# Mcontr_3.net
KiCad netlist of a schematic drawn in Altium Designer
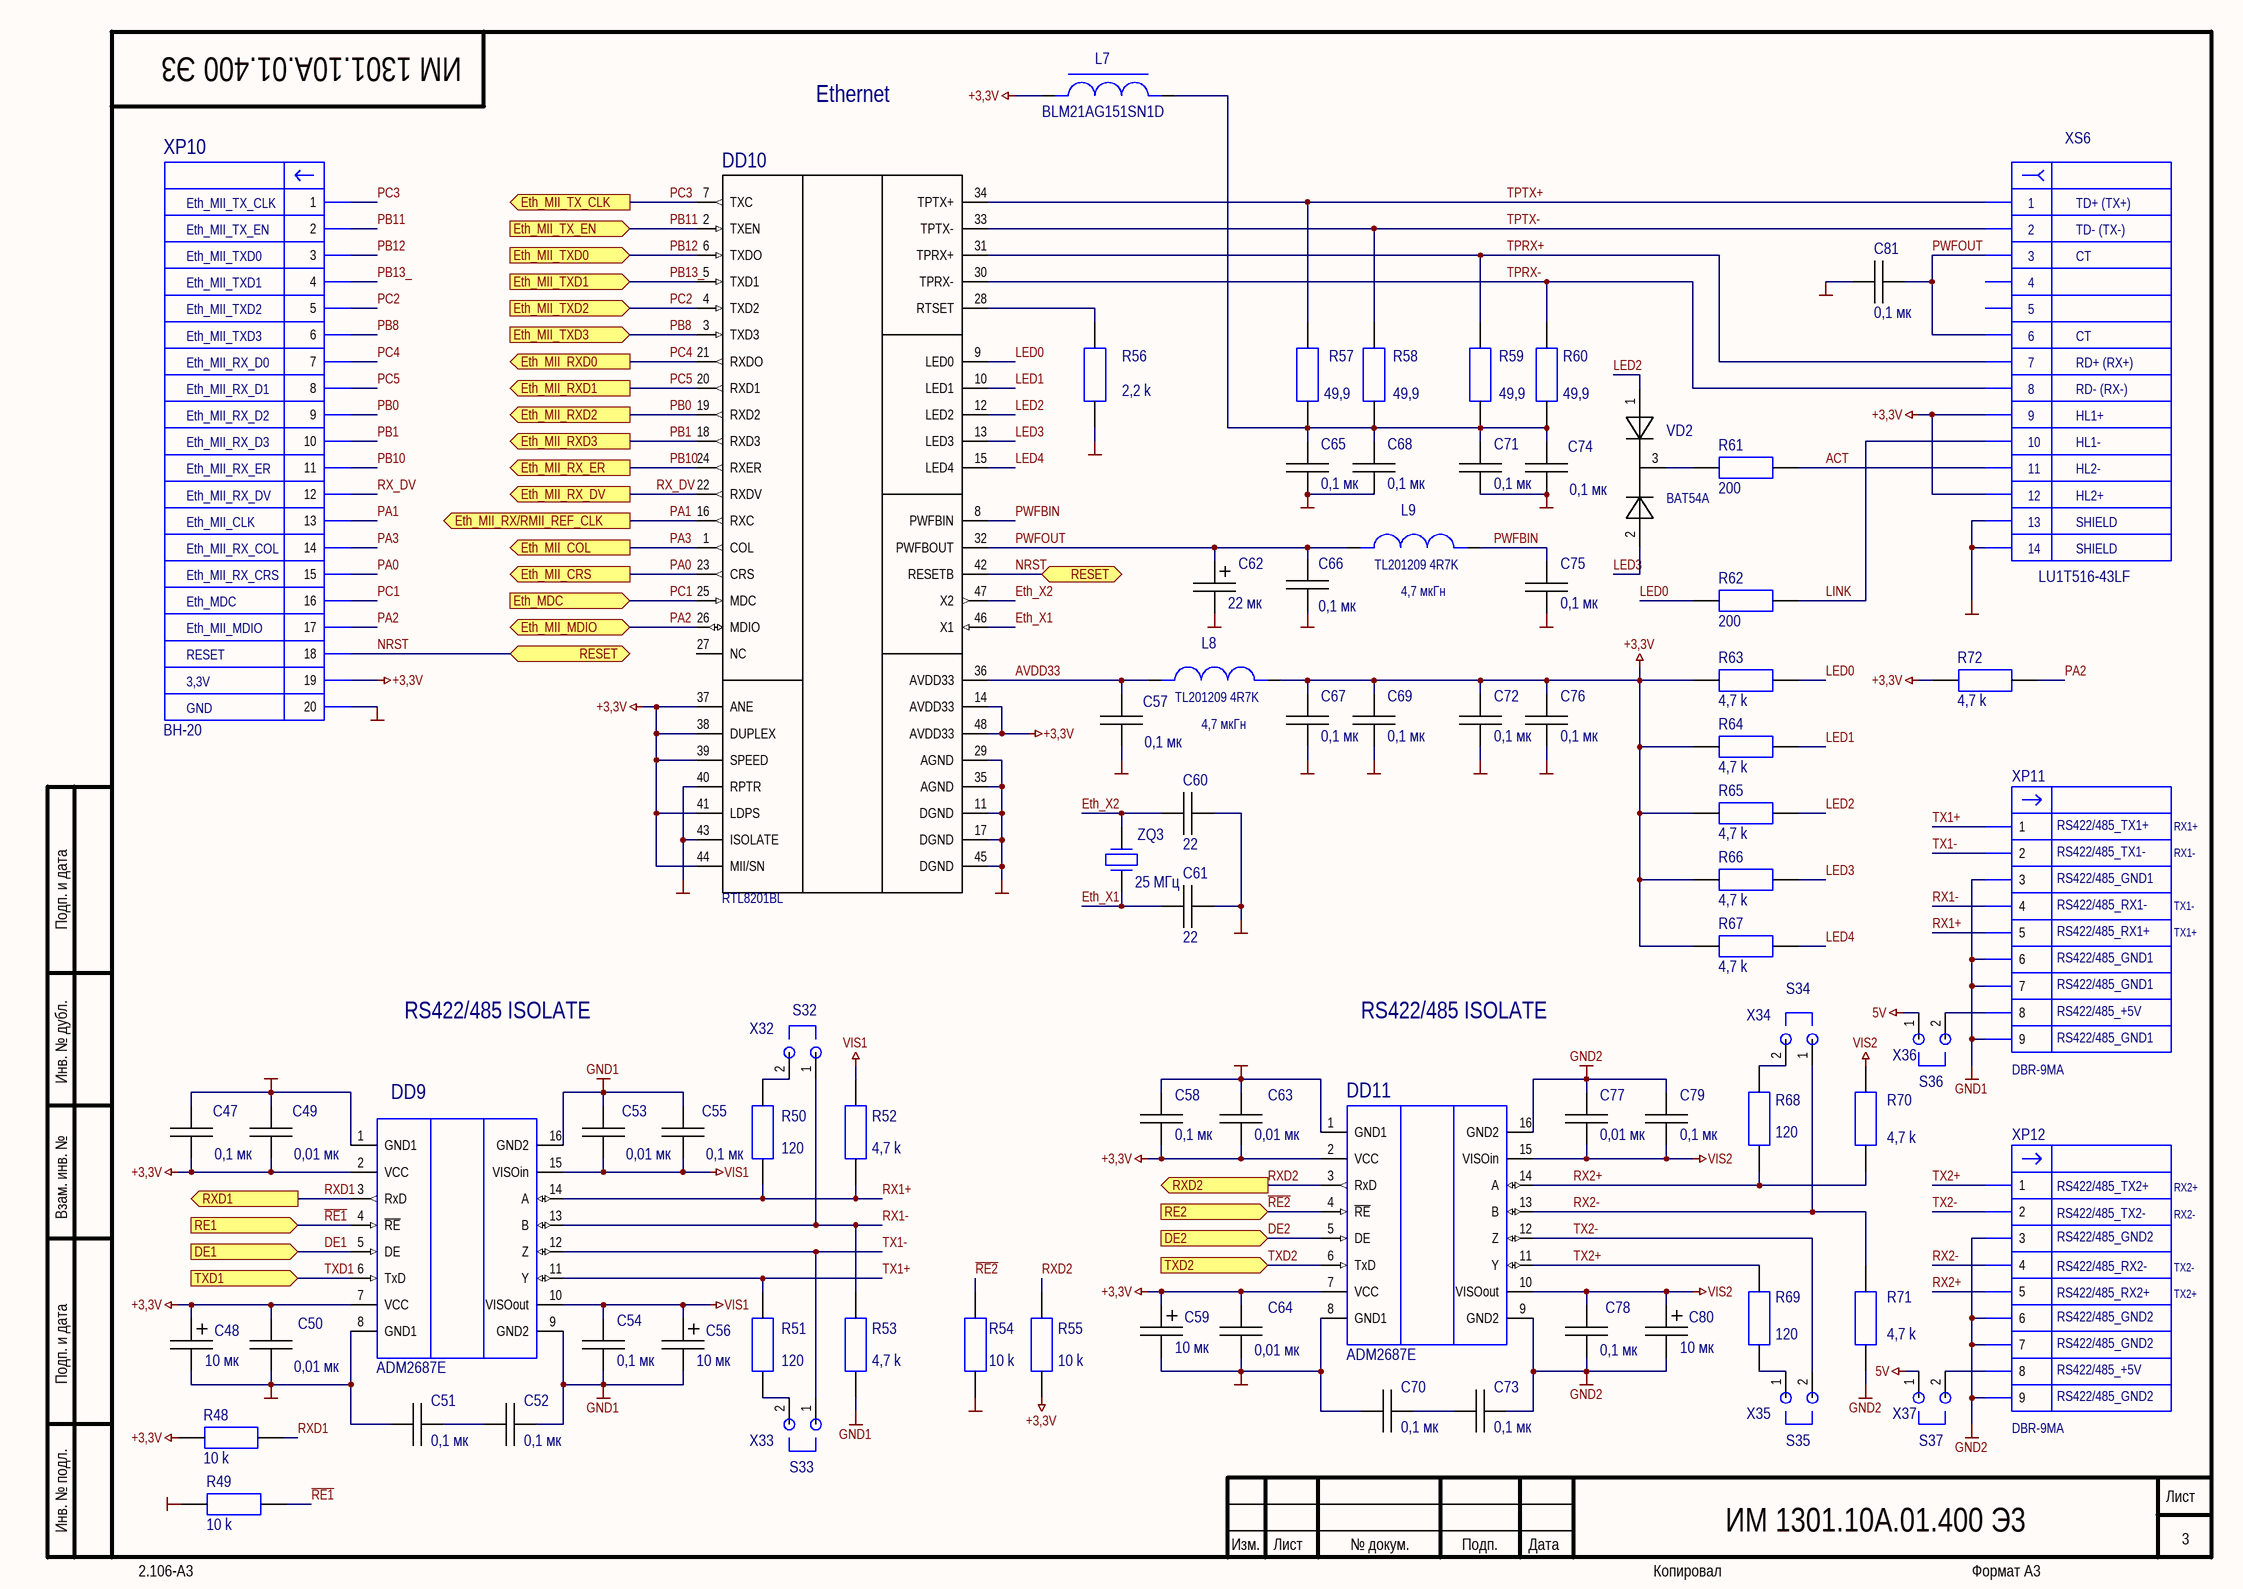
[diagram p0: Mcontr_3.SchDoc]

(export (version "E")
  (design (tool "Eeschema 10.0.6"))
  (components
    (comp (ref "C47")
      (value "0,1 мк")
      (footprint "CAPC_1206")
      (description "Capasitor")
      (fields (field (name "PART NUMBER") "C"))
      (libsource (lib "RLC_GOST") (part "C"))
    )
    (comp (ref "C48")
      (value "10 мк")
      (footprint "3216")
      (description "Capasitor_polar")
      (fields (field (name "PART NUMBER") "CapPol"))
      (libsource (lib "RLC_GOST") (part "CapPol"))
    )
    (comp (ref "C49")
      (value "0,01 мк")
      (footprint "CAPC_1206")
      (description "Capasitor")
      (fields (field (name "PART NUMBER") "C"))
      (libsource (lib "RLC_GOST") (part "C"))
    )
    (comp (ref "C50")
      (value "0,01 мк")
      (footprint "CAPC_1206")
      (description "Capasitor")
      (fields (field (name "PART NUMBER") "C"))
      (libsource (lib "RLC_GOST") (part "C"))
    )
    (comp (ref "C51")
      (value "0,1 мк")
      (footprint "CAPC_1206")
      (description "Capasitor")
      (fields (field (name "PART NUMBER") "C"))
      (libsource (lib "RLC_GOST") (part "C"))
    )
    (comp (ref "C52")
      (value "0,1 мк")
      (footprint "CAPC_1206")
      (description "Capasitor")
      (fields (field (name "PART NUMBER") "C"))
      (libsource (lib "RLC_GOST") (part "C"))
    )
    (comp (ref "C53")
      (value "0,01 мк")
      (footprint "CAPC_1206")
      (description "Capasitor")
      (fields (field (name "PART NUMBER") "C"))
      (libsource (lib "RLC_GOST") (part "C"))
    )
    (comp (ref "C54")
      (value "0,1 мк")
      (footprint "CAPC_1206")
      (description "Capasitor")
      (fields (field (name "PART NUMBER") "C"))
      (libsource (lib "RLC_GOST") (part "C"))
    )
    (comp (ref "C55")
      (value "0,1 мк")
      (footprint "CAPC_1206")
      (description "Capasitor")
      (fields (field (name "PART NUMBER") "C"))
      (libsource (lib "RLC_GOST") (part "C"))
    )
    (comp (ref "C56")
      (value "10 мк")
      (footprint "3216")
      (description "Capasitor_polar")
      (fields (field (name "PART NUMBER") "CapPol"))
      (libsource (lib "RLC_GOST") (part "CapPol"))
    )
    (comp (ref "C57")
      (value "0,1 мк")
      (footprint "CAPC_1206")
      (description "Capasitor")
      (fields (field (name "PART NUMBER") "C"))
      (libsource (lib "RLC_GOST") (part "C"))
    )
    (comp (ref "C58")
      (value "0,1 мк")
      (footprint "CAPC_1206")
      (description "Capasitor")
      (fields (field (name "PART NUMBER") "C"))
      (libsource (lib "RLC_GOST") (part "C"))
    )
    (comp (ref "C59")
      (value "10 мк")
      (footprint "3216")
      (description "Capasitor_polar")
      (fields (field (name "PART NUMBER") "CapPol"))
      (libsource (lib "RLC_GOST") (part "CapPol"))
    )
    (comp (ref "C60")
      (value "22")
      (footprint "CAPC_1206")
      (description "Capasitor")
      (libsource (lib "RLC_GOST") (part "C"))
    )
    (comp (ref "C61")
      (value "22")
      (footprint "CAPC_1206")
      (description "Capasitor")
      (libsource (lib "RLC_GOST") (part "C"))
    )
    (comp (ref "C62")
      (value "22 мк")
      (footprint "3216")
      (description "Capasitor_polar")
      (fields (field (name "PART NUMBER") "CapPol"))
      (libsource (lib "RLC_GOST") (part "CapPol"))
    )
    (comp (ref "C63")
      (value "0,01 мк")
      (footprint "CAPC_1206")
      (description "Capasitor")
      (fields (field (name "PART NUMBER") "C"))
      (libsource (lib "RLC_GOST") (part "C"))
    )
    (comp (ref "C64")
      (value "0,01 мк")
      (footprint "CAPC_1206")
      (description "Capasitor")
      (fields (field (name "PART NUMBER") "C"))
      (libsource (lib "RLC_GOST") (part "C"))
    )
    (comp (ref "C65")
      (value "0,1 мк")
      (footprint "CAPC_1206")
      (description "Capasitor")
      (fields (field (name "PART NUMBER") "C"))
      (libsource (lib "RLC_GOST") (part "C"))
    )
    (comp (ref "C66")
      (value "0,1 мк")
      (footprint "CAPC_1206")
      (description "Capasitor")
      (fields (field (name "PART NUMBER") "C"))
      (libsource (lib "RLC_GOST") (part "C"))
    )
    (comp (ref "C67")
      (value "0,1 мк")
      (footprint "CAPC_1206")
      (description "Capasitor")
      (fields (field (name "PART NUMBER") "C"))
      (libsource (lib "RLC_GOST") (part "C"))
    )
    (comp (ref "C68")
      (value "0,1 мк")
      (footprint "CAPC_1206")
      (description "Capasitor")
      (fields (field (name "PART NUMBER") "C"))
      (libsource (lib "RLC_GOST") (part "C"))
    )
    (comp (ref "C69")
      (value "0,1 мк")
      (footprint "CAPC_1206")
      (description "Capasitor")
      (fields (field (name "PART NUMBER") "C"))
      (libsource (lib "RLC_GOST") (part "C"))
    )
    (comp (ref "C70")
      (value "0,1 мк")
      (footprint "CAPC_1206")
      (description "Capasitor")
      (fields (field (name "PART NUMBER") "C"))
      (libsource (lib "RLC_GOST") (part "C"))
    )
    (comp (ref "C71")
      (value "0,1 мк")
      (footprint "CAPC_1206")
      (description "Capasitor")
      (fields (field (name "PART NUMBER") "C"))
      (libsource (lib "RLC_GOST") (part "C"))
    )
    (comp (ref "C72")
      (value "0,1 мк")
      (footprint "CAPC_1206")
      (description "Capasitor")
      (fields (field (name "PART NUMBER") "C"))
      (libsource (lib "RLC_GOST") (part "C"))
    )
    (comp (ref "C73")
      (value "0,1 мк")
      (footprint "CAPC_1206")
      (description "Capasitor")
      (fields (field (name "PART NUMBER") "C"))
      (libsource (lib "RLC_GOST") (part "C"))
    )
    (comp (ref "C74")
      (value "0,1 мк")
      (footprint "CAPC_1206")
      (description "Capasitor")
      (fields (field (name "PART NUMBER") "C"))
      (libsource (lib "RLC_GOST") (part "C"))
    )
    (comp (ref "C75")
      (value "0,1 мк")
      (footprint "CAPC_1206")
      (description "Capasitor")
      (fields (field (name "PART NUMBER") "C"))
      (libsource (lib "RLC_GOST") (part "C"))
    )
    (comp (ref "C76")
      (value "0,1 мк")
      (footprint "CAPC_1206")
      (description "Capasitor")
      (fields (field (name "PART NUMBER") "C"))
      (libsource (lib "RLC_GOST") (part "C"))
    )
    (comp (ref "C77")
      (value "0,01 мк")
      (footprint "CAPC_1206")
      (description "Capasitor")
      (fields (field (name "PART NUMBER") "C"))
      (libsource (lib "RLC_GOST") (part "C"))
    )
    (comp (ref "C78")
      (value "0,1 мк")
      (footprint "CAPC_1206")
      (description "Capasitor")
      (fields (field (name "PART NUMBER") "C"))
      (libsource (lib "RLC_GOST") (part "C"))
    )
    (comp (ref "C79")
      (value "0,1 мк")
      (footprint "CAPC_1206")
      (description "Capasitor")
      (fields (field (name "PART NUMBER") "C"))
      (libsource (lib "RLC_GOST") (part "C"))
    )
    (comp (ref "C80")
      (value "10 мк")
      (footprint "3216")
      (description "Capasitor_polar")
      (fields (field (name "PART NUMBER") "CapPol"))
      (libsource (lib "RLC_GOST") (part "CapPol"))
    )
    (comp (ref "C81")
      (value "0,1 мк")
      (footprint "CAPC_1206")
      (description "Capasitor")
      (fields (field (name "PART NUMBER") "C"))
      (libsource (lib "RLC_GOST") (part "C"))
    )
    (comp (ref "DD9")
      (value "ADM2687E")
      (footprint "SOIC_IC16")
      (description "RS422/RS485 transceivier 15 kV ESD Protection")
      (libsource (lib "Communication transceiver") (part "ADM2682E"))
    )
    (comp (ref "DD10")
      (value "RTL8201BL")
      (footprint "SQFP48")
      (description "Ethernet phyciever, 10/100M")
      (libsource (lib "Ethernet") (part "RTL8201BL"))
    )
    (comp (ref "DD11")
      (value "ADM2687E")
      (footprint "SOIC_IC16")
      (description "RS422/RS485 transceivier 15 kV ESD Protection")
      (libsource (lib "Communication transceiver") (part "ADM2682E"))
    )
    (comp (ref "L7")
      (value "BLM21AG151SN1D")
      (footprint "C0805")
      (description "Ferrite bead")
      (libsource (lib "RLC_GOST") (part "B"))
    )
    (comp (ref "L8")
      (value "TL201209 4R7K")
      (footprint "C0805")
      (description "Inductance")
      (fields (field (name "VALUE1") "4,7 мкГн"))
      (libsource (lib "RLC_GOST") (part "L"))
    )
    (comp (ref "L9")
      (value "TL201209 4R7K")
      (footprint "C0805")
      (description "Inductance")
      (fields (field (name "VALUE1") "4,7 мкГн"))
      (libsource (lib "RLC_GOST") (part "L"))
    )
    (comp (ref "R48")
      (value "10 k")
      (footprint "SMD_1206")
      (description "Resistor,2 Pin")
      (libsource (lib "RLC_GOST") (part "R_Gost"))
    )
    (comp (ref "R49")
      (value "10 k")
      (footprint "SMD_1206")
      (description "Resistor,2 Pin")
      (libsource (lib "RLC_GOST") (part "R_Gost"))
    )
    (comp (ref "R50")
      (value "120")
      (footprint "SMD_1206")
      (description "Resistor,2 Pin")
      (libsource (lib "RLC_GOST") (part "R_Gost"))
    )
    (comp (ref "R51")
      (value "120")
      (footprint "SMD_1206")
      (description "Resistor,2 Pin")
      (libsource (lib "RLC_GOST") (part "R_Gost"))
    )
    (comp (ref "R52")
      (value "4,7 k")
      (footprint "SMD_1206")
      (description "Resistor,2 Pin")
      (libsource (lib "RLC_GOST") (part "R_Gost"))
    )
    (comp (ref "R53")
      (value "4,7 k")
      (footprint "SMD_1206")
      (description "Resistor,2 Pin")
      (libsource (lib "RLC_GOST") (part "R_Gost"))
    )
    (comp (ref "R54")
      (value "10 k")
      (footprint "SMD_1206")
      (description "Resistor,2 Pin")
      (libsource (lib "RLC_GOST") (part "R_Gost"))
    )
    (comp (ref "R55")
      (value "10 k")
      (footprint "SMD_1206")
      (description "Resistor,2 Pin")
      (libsource (lib "RLC_GOST") (part "R_Gost"))
    )
    (comp (ref "R56")
      (value "2,2 k")
      (footprint "SMD_1206")
      (description "Resistor,2 Pin")
      (libsource (lib "RLC_GOST") (part "R_Gost"))
    )
    (comp (ref "R57")
      (value "49,9")
      (footprint "SMD_1206")
      (description "Resistor,2 Pin")
      (libsource (lib "RLC_GOST") (part "R_Gost"))
    )
    (comp (ref "R58")
      (value "49,9")
      (footprint "SMD_1206")
      (description "Resistor,2 Pin")
      (libsource (lib "RLC_GOST") (part "R_Gost"))
    )
    (comp (ref "R59")
      (value "49,9")
      (footprint "SMD_1206")
      (description "Resistor,2 Pin")
      (libsource (lib "RLC_GOST") (part "R_Gost"))
    )
    (comp (ref "R60")
      (value "49,9")
      (footprint "SMD_1206")
      (description "Resistor,2 Pin")
      (libsource (lib "RLC_GOST") (part "R_Gost"))
    )
    (comp (ref "R61")
      (value "200")
      (footprint "SMD_1206")
      (description "Resistor,2 Pin")
      (libsource (lib "RLC_GOST") (part "R_Gost"))
    )
    (comp (ref "R62")
      (value "200")
      (footprint "SMD_1206")
      (description "Resistor,2 Pin")
      (libsource (lib "RLC_GOST") (part "R_Gost"))
    )
    (comp (ref "R63")
      (value "4,7 k")
      (footprint "SMD_1206")
      (description "Resistor,2 Pin")
      (libsource (lib "RLC_GOST") (part "R_Gost"))
    )
    (comp (ref "R64")
      (value "4,7 k")
      (footprint "SMD_1206")
      (description "Resistor,2 Pin")
      (libsource (lib "RLC_GOST") (part "R_Gost"))
    )
    (comp (ref "R65")
      (value "4,7 k")
      (footprint "SMD_1206")
      (description "Resistor,2 Pin")
      (libsource (lib "RLC_GOST") (part "R_Gost"))
    )
    (comp (ref "R66")
      (value "4,7 k")
      (footprint "SMD_1206")
      (description "Resistor,2 Pin")
      (libsource (lib "RLC_GOST") (part "R_Gost"))
    )
    (comp (ref "R67")
      (value "4,7 k")
      (footprint "SMD_1206")
      (description "Resistor,2 Pin")
      (libsource (lib "RLC_GOST") (part "R_Gost"))
    )
    (comp (ref "R68")
      (value "120")
      (footprint "SMD_1206")
      (description "Resistor,2 Pin")
      (libsource (lib "RLC_GOST") (part "R_Gost"))
    )
    (comp (ref "R69")
      (value "120")
      (footprint "SMD_1206")
      (description "Resistor,2 Pin")
      (libsource (lib "RLC_GOST") (part "R_Gost"))
    )
    (comp (ref "R70")
      (value "4,7 k")
      (footprint "SMD_1206")
      (description "Resistor,2 Pin")
      (libsource (lib "RLC_GOST") (part "R_Gost"))
    )
    (comp (ref "R71")
      (value "4,7 k")
      (footprint "SMD_1206")
      (description "Resistor,2 Pin")
      (libsource (lib "RLC_GOST") (part "R_Gost"))
    )
    (comp (ref "R72")
      (value "4,7 k")
      (footprint "SMD_1206")
      (description "Resistor,2 Pin")
      (libsource (lib "RLC_GOST") (part "R_Gost"))
    )
    (comp (ref "VD2")
      (value "BAT54A")
      (footprint "SOT23")
      (description "Diod Schottky, 3 pin")
      (fields (field (name "MANUFACTURER") "Fairchild"))
      (libsource (lib "Diod") (part "BS40-06"))
    )
    (comp (ref "X32")
      (value "PLS-02")
      (footprint "PLS-2")
      (fields (field (name "JAMPER") "S32"))
      (libsource (lib "Connectors") (part "J2"))
    )
    (comp (ref "X33")
      (value "PLS-02")
      (footprint "PLS-2")
      (fields (field (name "JAMPER") "S33"))
      (libsource (lib "Connectors") (part "J2"))
    )
    (comp (ref "X34")
      (value "PLS-02")
      (footprint "PLS-2")
      (fields (field (name "JAMPER") "S34"))
      (libsource (lib "Connectors") (part "J2"))
    )
    (comp (ref "X35")
      (value "PLS-02")
      (footprint "PLS-2")
      (fields (field (name "JAMPER") "S35"))
      (libsource (lib "Connectors") (part "J2"))
    )
    (comp (ref "X36")
      (value "PLS-02")
      (footprint "PLS-2")
      (fields (field (name "JAMPER") "S36"))
      (libsource (lib "Connectors") (part "J2"))
    )
    (comp (ref "X37")
      (value "PLS-02")
      (footprint "PLS-2")
      (fields (field (name "JAMPER") "S37"))
      (libsource (lib "Connectors") (part "J2"))
    )
    (comp (ref "XP10") (value "BH-20") (footprint "PLD-20") (libsource (lib "Connectors") (part "BH-20")))
    (comp (ref "XP11")
      (value "DBR-9MA")
      (footprint "DB9M")
      (description "X9")
      (fields (field (name "MANUFACTURER") "Ningbo"))
      (libsource (lib "Connectors") (part "X9"))
    )
    (comp (ref "XP12")
      (value "DBR-9MA")
      (footprint "DB9M")
      (description "X9")
      (fields (field (name "MANUFACTURER") "Ningbo"))
      (libsource (lib "Connectors") (part "X9"))
    )
    (comp (ref "XS6")
      (value "LU1T516-43LF")
      (footprint "LU1T516-43LF")
      (description "RJ45")
      (libsource (lib "Connectors") (part "RJ45"))
    )
    (comp (ref "ZQ3")
      (value "25 МГц")
      (footprint "HC-49U_5mm")
      (description "OSC")
      (libsource (lib "Resonators") (part "OSC"))
    )
  )
  (nets
    (net (code "1") (name "+3,3V") (class "Default")
      (node (ref "C47") (pin "1") (pinfunction "1_1") (pintype "passive"))
      (node (ref "C48") (pin "1") (pinfunction "+_1") (pintype "passive"))
      (node (ref "C49") (pin "1") (pinfunction "1_1") (pintype "passive"))
      (node (ref "C50") (pin "2") (pinfunction "2_2") (pintype "passive"))
      (node (ref "C58") (pin "1") (pinfunction "1_1") (pintype "passive"))
      (node (ref "C59") (pin "1") (pinfunction "+_1") (pintype "passive"))
      (node (ref "C63") (pin "1") (pinfunction "1_1") (pintype "passive"))
      (node (ref "C64") (pin "2") (pinfunction "2_2") (pintype "passive"))
      (node (ref "C67") (pin "2") (pinfunction "2_2") (pintype "passive"))
      (node (ref "C69") (pin "2") (pinfunction "2_2") (pintype "passive"))
      (node (ref "C72") (pin "2") (pinfunction "2_2") (pintype "passive"))
      (node (ref "C76") (pin "2") (pinfunction "2_2") (pintype "passive"))
      (node (ref "DD10") (pin "14") (pinfunction "AVDD33_14") (pintype "power_in"))
      (node (ref "DD10") (pin "37") (pinfunction "ANE_37") (pintype "passive"))
      (node (ref "DD10") (pin "38") (pinfunction "DUPLEX_38") (pintype "passive"))
      (node (ref "DD10") (pin "39") (pinfunction "SPEED_39") (pintype "passive"))
      (node (ref "DD10") (pin "41") (pinfunction "LDPS_41") (pintype "passive"))
      (node (ref "DD10") (pin "44") (pinfunction "MII/SN_44") (pintype "passive"))
      (node (ref "DD10") (pin "48") (pinfunction "AVDD33_48") (pintype "power_in"))
      (node (ref "DD11") (pin "2") (pinfunction "VCC_2") (pintype "power_in"))
      (node (ref "DD11") (pin "7") (pinfunction "VCC_7") (pintype "power_in"))
      (node (ref "DD9") (pin "2") (pinfunction "VCC_2") (pintype "power_in"))
      (node (ref "DD9") (pin "7") (pinfunction "VCC_7") (pintype "power_in"))
      (node (ref "L7") (pin "1") (pinfunction "1_1") (pintype "passive"))
      (node (ref "L8") (pin "2") (pinfunction "2_2") (pintype "passive"))
      (node (ref "R48") (pin "1") (pinfunction "1_1") (pintype "passive"))
      (node (ref "R55") (pin "1") (pinfunction "1_1") (pintype "passive"))
      (node (ref "R63") (pin "1") (pinfunction "1_1") (pintype "passive"))
      (node (ref "R64") (pin "1") (pinfunction "1_1") (pintype "passive"))
      (node (ref "R65") (pin "1") (pinfunction "1_1") (pintype "passive"))
      (node (ref "R66") (pin "1") (pinfunction "1_1") (pintype "passive"))
      (node (ref "R67") (pin "1") (pinfunction "1_1") (pintype "passive"))
      (node (ref "R72") (pin "2") (pinfunction "2_2") (pintype "passive"))
      (node (ref "XP10") (pin "19") (pinfunction "19_19") (pintype "passive"))
      (node (ref "XS6") (pin "12") (pinfunction "12_12") (pintype "passive"))
      (node (ref "XS6") (pin "9") (pinfunction "9_9") (pintype "passive"))
    )
    (net (code "2") (name "/ACT") (class "Default")
      (node (ref "R61") (pin "1") (pinfunction "1_1") (pintype "passive"))
      (node (ref "XS6") (pin "11") (pinfunction "11_11") (pintype "passive"))
    )
    (net (code "3") (name "/AVDD33") (class "Default")
      (node (ref "C57") (pin "2") (pinfunction "2_2") (pintype "passive"))
      (node (ref "DD10") (pin "36") (pinfunction "AVDD33_36") (pintype "power_in"))
      (node (ref "L8") (pin "1") (pinfunction "1_1") (pintype "passive"))
    )
    (net (code "4") (name "/DE1") (class "Default")
      (node (ref "DD9") (pin "5") (pinfunction "DE_5") (pintype "input"))
    )
    (net (code "5") (name "/DE2") (class "Default")
      (node (ref "DD11") (pin "5") (pinfunction "DE_5") (pintype "input"))
    )
    (net (code "6") (name "/Eth_X1") (class "Default")
      (node (ref "C61") (pin "2") (pinfunction "2_2") (pintype "passive"))
      (node (ref "DD10") (pin "46") (pinfunction "X1_46") (pintype "input"))
      (node (ref "ZQ3") (pin "1") (pinfunction "1_1") (pintype "passive"))
    )
    (net (code "7") (name "/Eth_X2") (class "Default")
      (node (ref "C60") (pin "2") (pinfunction "2_2") (pintype "passive"))
      (node (ref "DD10") (pin "47") (pinfunction "X2_47") (pintype "output"))
      (node (ref "ZQ3") (pin "2") (pinfunction "2_2") (pintype "passive"))
    )
    (net (code "8") (name "/LED0") (class "Default")
      (node (ref "DD10") (pin "9") (pinfunction "LED0_9") (pintype "passive"))
      (node (ref "R62") (pin "2") (pinfunction "2_2") (pintype "passive"))
      (node (ref "R63") (pin "2") (pinfunction "2_2") (pintype "passive"))
    )
    (net (code "9") (name "/LED1") (class "Default")
      (node (ref "DD10") (pin "10") (pinfunction "LED1_10") (pintype "passive"))
      (node (ref "R64") (pin "2") (pinfunction "2_2") (pintype "passive"))
    )
    (net (code "10") (name "/LED2") (class "Default")
      (node (ref "DD10") (pin "12") (pinfunction "LED2_12") (pintype "passive"))
      (node (ref "R65") (pin "2") (pinfunction "2_2") (pintype "passive"))
      (node (ref "VD2") (pin "1") (pinfunction "+_1") (pintype "passive"))
    )
    (net (code "11") (name "/LED3") (class "Default")
      (node (ref "DD10") (pin "13") (pinfunction "LED3_13") (pintype "passive"))
      (node (ref "R66") (pin "2") (pinfunction "2_2") (pintype "passive"))
      (node (ref "VD2") (pin "2") (pinfunction "-_2") (pintype "passive"))
    )
    (net (code "12") (name "/LED4") (class "Default")
      (node (ref "DD10") (pin "15") (pinfunction "LED4_15") (pintype "passive"))
      (node (ref "R67") (pin "2") (pinfunction "2_2") (pintype "passive"))
    )
    (net (code "13") (name "/LINK") (class "Default")
      (node (ref "R62") (pin "1") (pinfunction "1_1") (pintype "passive"))
      (node (ref "XS6") (pin "10") (pinfunction "10_10") (pintype "passive"))
    )
    (net (code "14") (name "/NRST") (class "Default")
      (node (ref "DD10") (pin "42") (pinfunction "RESETB_42") (pintype "passive"))
      (node (ref "XP10") (pin "18") (pinfunction "18_18") (pintype "passive"))
    )
    (net (code "15") (name "/PA0") (class "Default")
      (node (ref "DD10") (pin "23") (pinfunction "CRS_23") (pintype "output"))
      (node (ref "XP10") (pin "15") (pinfunction "15_15") (pintype "passive"))
    )
    (net (code "16") (name "/PA1") (class "Default")
      (node (ref "DD10") (pin "16") (pinfunction "RXC_16") (pintype "output"))
      (node (ref "XP10") (pin "13") (pinfunction "13_13") (pintype "passive"))
    )
    (net (code "17") (name "/PA2") (class "Default")
      (node (ref "DD10") (pin "26") (pinfunction "MDIO_26") (pintype "bidirectional"))
      (node (ref "R72") (pin "1") (pinfunction "1_1") (pintype "passive"))
      (node (ref "XP10") (pin "17") (pinfunction "17_17") (pintype "passive"))
    )
    (net (code "18") (name "/PA3") (class "Default")
      (node (ref "DD10") (pin "1") (pinfunction "COL_1") (pintype "output"))
      (node (ref "XP10") (pin "14") (pinfunction "14_14") (pintype "passive"))
    )
    (net (code "19") (name "/PB0") (class "Default")
      (node (ref "DD10") (pin "19") (pinfunction "RXD2_19") (pintype "output"))
      (node (ref "XP10") (pin "9") (pinfunction "9_9") (pintype "passive"))
    )
    (net (code "20") (name "/PB1") (class "Default")
      (node (ref "DD10") (pin "18") (pinfunction "RXD3_18") (pintype "output"))
      (node (ref "XP10") (pin "10") (pinfunction "10_10") (pintype "passive"))
    )
    (net (code "21") (name "/PB8") (class "Default")
      (node (ref "DD10") (pin "3") (pinfunction "TXD3_3") (pintype "input"))
      (node (ref "XP10") (pin "6") (pinfunction "6_6") (pintype "passive"))
    )
    (net (code "22") (name "/PB10") (class "Default")
      (node (ref "DD10") (pin "24") (pinfunction "RXER_24") (pintype "output"))
      (node (ref "XP10") (pin "11") (pinfunction "11_11") (pintype "passive"))
    )
    (net (code "23") (name "/PB11") (class "Default")
      (node (ref "DD10") (pin "2") (pinfunction "TXEN_2") (pintype "input"))
      (node (ref "XP10") (pin "2") (pinfunction "2_2") (pintype "passive"))
    )
    (net (code "24") (name "/PB12") (class "Default")
      (node (ref "DD10") (pin "6") (pinfunction "TXDO_6") (pintype "input"))
      (node (ref "XP10") (pin "3") (pinfunction "3_3") (pintype "passive"))
    )
    (net (code "25") (name "/PB13_") (class "Default")
      (node (ref "DD10") (pin "5") (pinfunction "TXD1_5") (pintype "input"))
      (node (ref "XP10") (pin "4") (pinfunction "4_4") (pintype "passive"))
    )
    (net (code "26") (name "/PC1") (class "Default")
      (node (ref "DD10") (pin "25") (pinfunction "MDC_25") (pintype "input"))
      (node (ref "XP10") (pin "16") (pinfunction "16_16") (pintype "passive"))
    )
    (net (code "27") (name "/PC2") (class "Default")
      (node (ref "DD10") (pin "4") (pinfunction "TXD2_4") (pintype "input"))
      (node (ref "XP10") (pin "5") (pinfunction "5_5") (pintype "passive"))
    )
    (net (code "28") (name "/PC3") (class "Default")
      (node (ref "DD10") (pin "7") (pinfunction "TXC_7") (pintype "output"))
      (node (ref "XP10") (pin "1") (pinfunction "1_1") (pintype "passive"))
    )
    (net (code "29") (name "/PC4") (class "Default")
      (node (ref "DD10") (pin "21") (pinfunction "RXDO_21") (pintype "output"))
      (node (ref "XP10") (pin "7") (pinfunction "7_7") (pintype "passive"))
    )
    (net (code "30") (name "/PC5") (class "Default")
      (node (ref "DD10") (pin "20") (pinfunction "RXD1_20") (pintype "output"))
      (node (ref "XP10") (pin "8") (pinfunction "8_8") (pintype "passive"))
    )
    (net (code "31") (name "/PWFBIN") (class "Default")
      (node (ref "C75") (pin "2") (pinfunction "2_2") (pintype "passive"))
      (node (ref "DD10") (pin "8") (pinfunction "PWFBIN_8") (pintype "passive"))
      (node (ref "L9") (pin "2") (pinfunction "2_2") (pintype "passive"))
    )
    (net (code "32") (name "/PWFOUT") (class "Default")
      (node (ref "C62") (pin "1") (pinfunction "+_1") (pintype "passive"))
      (node (ref "C66") (pin "2") (pinfunction "2_2") (pintype "passive"))
      (node (ref "C81") (pin "1") (pinfunction "1_1") (pintype "passive"))
      (node (ref "DD10") (pin "32") (pinfunction "PWFBOUT_32") (pintype "passive"))
      (node (ref "L9") (pin "1") (pinfunction "1_1") (pintype "passive"))
      (node (ref "XS6") (pin "3") (pinfunction "3_3") (pintype "passive"))
      (node (ref "XS6") (pin "6") (pinfunction "6_6") (pintype "passive"))
    )
    (net (code "33") (name "/RE1") (class "Default")
      (node (ref "DD9") (pin "4") (pinfunction "RE_4") (pintype "input"))
      (node (ref "R49") (pin "2") (pinfunction "2_2") (pintype "passive"))
    )
    (net (code "34") (name "/RE2") (class "Default")
      (node (ref "DD11") (pin "4") (pinfunction "RE_4") (pintype "input"))
      (node (ref "R54") (pin "2") (pinfunction "2_2") (pintype "passive"))
    )
    (net (code "35") (name "/RX1+") (class "Default")
      (node (ref "DD9") (pin "14") (pinfunction "A_14") (pintype "bidirectional"))
      (node (ref "R50") (pin "2") (pinfunction "2_2") (pintype "passive"))
      (node (ref "R52") (pin "1") (pinfunction "1_1") (pintype "passive"))
      (node (ref "XP11") (pin "5") (pinfunction "5_5") (pintype "passive"))
    )
    (net (code "36") (name "/RX1-") (class "Default")
      (node (ref "DD9") (pin "13") (pinfunction "B_13") (pintype "bidirectional"))
      (node (ref "R53") (pin "1") (pinfunction "1_1") (pintype "passive"))
      (node (ref "X32") (pin "1") (pinfunction "1_1") (pintype "passive"))
      (node (ref "XP11") (pin "4") (pinfunction "4_4") (pintype "passive"))
    )
    (net (code "37") (name "/RX2+") (class "Default")
      (node (ref "DD11") (pin "14") (pinfunction "A_14") (pintype "bidirectional"))
      (node (ref "R68") (pin "2") (pinfunction "2_2") (pintype "passive"))
      (node (ref "R70") (pin "1") (pinfunction "1_1") (pintype "passive"))
      (node (ref "XP12") (pin "5") (pinfunction "5_5") (pintype "passive"))
    )
    (net (code "38") (name "/RX2-") (class "Default")
      (node (ref "DD11") (pin "13") (pinfunction "B_13") (pintype "bidirectional"))
      (node (ref "R71") (pin "1") (pinfunction "1_1") (pintype "passive"))
      (node (ref "X34") (pin "1") (pinfunction "1_1") (pintype "passive"))
      (node (ref "XP12") (pin "4") (pinfunction "4_4") (pintype "passive"))
    )
    (net (code "39") (name "/RXD1") (class "Default")
      (node (ref "DD9") (pin "3") (pinfunction "RxD_3") (pintype "output"))
      (node (ref "R48") (pin "2") (pinfunction "2_2") (pintype "passive"))
    )
    (net (code "40") (name "/RXD2") (class "Default")
      (node (ref "DD11") (pin "3") (pinfunction "RxD_3") (pintype "output"))
      (node (ref "R55") (pin "2") (pinfunction "2_2") (pintype "passive"))
    )
    (net (code "41") (name "/RX_DV") (class "Default")
      (node (ref "DD10") (pin "22") (pinfunction "RXDV_22") (pintype "output"))
      (node (ref "XP10") (pin "12") (pinfunction "12_12") (pintype "passive"))
    )
    (net (code "42") (name "/TPRX+") (class "Default")
      (node (ref "DD10") (pin "31") (pinfunction "TPRX+_31") (pintype "passive"))
      (node (ref "R59") (pin "2") (pinfunction "2_2") (pintype "passive"))
      (node (ref "XS6") (pin "7") (pinfunction "7_7") (pintype "passive"))
    )
    (net (code "43") (name "/TPRX-") (class "Default")
      (node (ref "DD10") (pin "30") (pinfunction "TPRX-_30") (pintype "passive"))
      (node (ref "R60") (pin "2") (pinfunction "2_2") (pintype "passive"))
      (node (ref "XS6") (pin "8") (pinfunction "8_8") (pintype "passive"))
    )
    (net (code "44") (name "/TPTX+") (class "Default")
      (node (ref "DD10") (pin "34") (pinfunction "TPTX+_34") (pintype "passive"))
      (node (ref "R57") (pin "2") (pinfunction "2_2") (pintype "passive"))
      (node (ref "XS6") (pin "1") (pinfunction "1_1") (pintype "passive"))
    )
    (net (code "45") (name "/TPTX-") (class "Default")
      (node (ref "DD10") (pin "33") (pinfunction "TPTX-_33") (pintype "passive"))
      (node (ref "R58") (pin "2") (pinfunction "2_2") (pintype "passive"))
      (node (ref "XS6") (pin "2") (pinfunction "2_2") (pintype "passive"))
    )
    (net (code "46") (name "/TX1+") (class "Default")
      (node (ref "DD9") (pin "11") (pinfunction "Y_11") (pintype "bidirectional"))
      (node (ref "R51") (pin "1") (pinfunction "1_1") (pintype "passive"))
      (node (ref "XP11") (pin "1") (pinfunction "1_1") (pintype "passive"))
    )
    (net (code "47") (name "/TX1-") (class "Default")
      (node (ref "DD9") (pin "12") (pinfunction "Z_12") (pintype "bidirectional"))
      (node (ref "X33") (pin "1") (pinfunction "1_1") (pintype "passive"))
      (node (ref "XP11") (pin "2") (pinfunction "2_2") (pintype "passive"))
    )
    (net (code "48") (name "/TX2+") (class "Default")
      (node (ref "DD11") (pin "11") (pinfunction "Y_11") (pintype "bidirectional"))
      (node (ref "R69") (pin "1") (pinfunction "1_1") (pintype "passive"))
      (node (ref "XP12") (pin "1") (pinfunction "1_1") (pintype "passive"))
    )
    (net (code "49") (name "/TX2-") (class "Default")
      (node (ref "DD11") (pin "12") (pinfunction "Z_12") (pintype "bidirectional"))
      (node (ref "X35") (pin "2") (pinfunction "2_2") (pintype "passive"))
      (node (ref "XP12") (pin "2") (pinfunction "2_2") (pintype "passive"))
    )
    (net (code "50") (name "/TXD1") (class "Default")
      (node (ref "DD9") (pin "6") (pinfunction "TxD_6") (pintype "input"))
    )
    (net (code "51") (name "/TXD2") (class "Default")
      (node (ref "DD11") (pin "6") (pinfunction "TxD_6") (pintype "input"))
    )
    (net (code "52") (name "5V") (class "Default")
      (node (ref "X36") (pin "1") (pinfunction "1_1") (pintype "passive"))
      (node (ref "X37") (pin "1") (pinfunction "1_1") (pintype "passive"))
    )
    (net (code "53") (name "GND") (class "Default")
      (node (ref "C47") (pin "2") (pinfunction "2_2") (pintype "passive"))
      (node (ref "C48") (pin "2") (pinfunction "-_2") (pintype "passive"))
      (node (ref "C49") (pin "2") (pinfunction "2_2") (pintype "passive"))
      (node (ref "C50") (pin "1") (pinfunction "1_1") (pintype "passive"))
      (node (ref "C51") (pin "2") (pinfunction "2_2") (pintype "passive"))
      (node (ref "C57") (pin "1") (pinfunction "1_1") (pintype "passive"))
      (node (ref "C58") (pin "2") (pinfunction "2_2") (pintype "passive"))
      (node (ref "C59") (pin "2") (pinfunction "-_2") (pintype "passive"))
      (node (ref "C60") (pin "1") (pinfunction "1_1") (pintype "passive"))
      (node (ref "C61") (pin "1") (pinfunction "1_1") (pintype "passive"))
      (node (ref "C62") (pin "2") (pinfunction "-_2") (pintype "passive"))
      (node (ref "C63") (pin "2") (pinfunction "2_2") (pintype "passive"))
      (node (ref "C64") (pin "1") (pinfunction "1_1") (pintype "passive"))
      (node (ref "C65") (pin "1") (pinfunction "1_1") (pintype "passive"))
      (node (ref "C66") (pin "1") (pinfunction "1_1") (pintype "passive"))
      (node (ref "C67") (pin "1") (pinfunction "1_1") (pintype "passive"))
      (node (ref "C68") (pin "1") (pinfunction "1_1") (pintype "passive"))
      (node (ref "C69") (pin "1") (pinfunction "1_1") (pintype "passive"))
      (node (ref "C70") (pin "2") (pinfunction "2_2") (pintype "passive"))
      (node (ref "C71") (pin "1") (pinfunction "1_1") (pintype "passive"))
      (node (ref "C72") (pin "1") (pinfunction "1_1") (pintype "passive"))
      (node (ref "C74") (pin "1") (pinfunction "1_1") (pintype "passive"))
      (node (ref "C75") (pin "1") (pinfunction "1_1") (pintype "passive"))
      (node (ref "C76") (pin "1") (pinfunction "1_1") (pintype "passive"))
      (node (ref "C81") (pin "2") (pinfunction "2_2") (pintype "passive"))
      (node (ref "DD10") (pin "11") (pinfunction "DGND_11") (pintype "power_in"))
      (node (ref "DD10") (pin "17") (pinfunction "DGND_17") (pintype "power_in"))
      (node (ref "DD10") (pin "29") (pinfunction "AGND_29") (pintype "power_in"))
      (node (ref "DD10") (pin "35") (pinfunction "AGND_35") (pintype "power_in"))
      (node (ref "DD10") (pin "40") (pinfunction "RPTR_40") (pintype "passive"))
      (node (ref "DD10") (pin "43") (pinfunction "ISOLATE_43") (pintype "passive"))
      (node (ref "DD10") (pin "45") (pinfunction "DGND_45") (pintype "power_in"))
      (node (ref "DD11") (pin "1") (pinfunction "GND1_1") (pintype "power_in"))
      (node (ref "DD11") (pin "8") (pinfunction "GND1_8") (pintype "power_in"))
      (node (ref "DD9") (pin "1") (pinfunction "GND1_1") (pintype "power_in"))
      (node (ref "DD9") (pin "8") (pinfunction "GND1_8") (pintype "power_in"))
      (node (ref "R49") (pin "1") (pinfunction "1_1") (pintype "passive"))
      (node (ref "R54") (pin "1") (pinfunction "1_1") (pintype "passive"))
      (node (ref "R56") (pin "1") (pinfunction "1_1") (pintype "passive"))
      (node (ref "XP10") (pin "20") (pinfunction "20_20") (pintype "passive"))
      (node (ref "XS6") (pin "13") (pinfunction "13_13") (pintype "passive"))
      (node (ref "XS6") (pin "14") (pinfunction "14_14") (pintype "passive"))
    )
    (net (code "54") (name "GND1") (class "Default")
      (node (ref "C52") (pin "1") (pinfunction "1_1") (pintype "passive"))
      (node (ref "C53") (pin "2") (pinfunction "2_2") (pintype "passive"))
      (node (ref "C54") (pin "1") (pinfunction "1_1") (pintype "passive"))
      (node (ref "C55") (pin "2") (pinfunction "2_2") (pintype "passive"))
      (node (ref "C56") (pin "2") (pinfunction "-_2") (pintype "passive"))
      (node (ref "DD9") (pin "16") (pinfunction "GND2_16") (pintype "power_in"))
      (node (ref "DD9") (pin "9") (pinfunction "GND2_9") (pintype "power_in"))
      (node (ref "R53") (pin "2") (pinfunction "2_2") (pintype "passive"))
      (node (ref "XP11") (pin "3") (pinfunction "3_3") (pintype "passive"))
      (node (ref "XP11") (pin "6") (pinfunction "6_6") (pintype "passive"))
      (node (ref "XP11") (pin "7") (pinfunction "7_7") (pintype "passive"))
      (node (ref "XP11") (pin "9") (pinfunction "9_9") (pintype "passive"))
    )
    (net (code "55") (name "GND2") (class "Default")
      (node (ref "C73") (pin "1") (pinfunction "1_1") (pintype "passive"))
      (node (ref "C77") (pin "2") (pinfunction "2_2") (pintype "passive"))
      (node (ref "C78") (pin "1") (pinfunction "1_1") (pintype "passive"))
      (node (ref "C79") (pin "2") (pinfunction "2_2") (pintype "passive"))
      (node (ref "C80") (pin "2") (pinfunction "-_2") (pintype "passive"))
      (node (ref "DD11") (pin "16") (pinfunction "GND2_16") (pintype "power_in"))
      (node (ref "DD11") (pin "9") (pinfunction "GND2_9") (pintype "power_in"))
      (node (ref "R71") (pin "2") (pinfunction "2_2") (pintype "passive"))
      (node (ref "XP12") (pin "3") (pinfunction "3_3") (pintype "passive"))
      (node (ref "XP12") (pin "6") (pinfunction "6_6") (pintype "passive"))
      (node (ref "XP12") (pin "7") (pinfunction "7_7") (pintype "passive"))
      (node (ref "XP12") (pin "9") (pinfunction "9_9") (pintype "passive"))
    )
    (net (code "56") (name "Net-(C51-Pad1)") (class "Default")
      (node (ref "C51") (pin "1") (pinfunction "1_1") (pintype "passive"))
      (node (ref "C52") (pin "2") (pinfunction "2_2") (pintype "passive"))
    )
    (net (code "57") (name "Net-(C65-Pad2)") (class "Default")
      (node (ref "C65") (pin "2") (pinfunction "2_2") (pintype "passive"))
      (node (ref "C68") (pin "2") (pinfunction "2_2") (pintype "passive"))
      (node (ref "C71") (pin "2") (pinfunction "2_2") (pintype "passive"))
      (node (ref "C74") (pin "2") (pinfunction "2_2") (pintype "passive"))
      (node (ref "L7") (pin "2") (pinfunction "2_2") (pintype "passive"))
      (node (ref "R57") (pin "1") (pinfunction "1_1") (pintype "passive"))
      (node (ref "R58") (pin "1") (pinfunction "1_1") (pintype "passive"))
      (node (ref "R59") (pin "1") (pinfunction "1_1") (pintype "passive"))
      (node (ref "R60") (pin "1") (pinfunction "1_1") (pintype "passive"))
    )
    (net (code "58") (name "Net-(C70-Pad1)") (class "Default")
      (node (ref "C70") (pin "1") (pinfunction "1_1") (pintype "passive"))
      (node (ref "C73") (pin "2") (pinfunction "2_2") (pintype "passive"))
    )
    (net (code "59") (name "Net-(DD10-RTSET)") (class "Default")
      (node (ref "DD10") (pin "28") (pinfunction "RTSET_28") (pintype "passive"))
      (node (ref "R56") (pin "2") (pinfunction "2_2") (pintype "passive"))
    )
    (net (code "60") (name "Net-(R50-Pad1)") (class "Default")
      (node (ref "R50") (pin "1") (pinfunction "1_1") (pintype "passive"))
      (node (ref "X32") (pin "2") (pinfunction "2_2") (pintype "passive"))
    )
    (net (code "61") (name "Net-(R51-Pad2)") (class "Default")
      (node (ref "R51") (pin "2") (pinfunction "2_2") (pintype "passive"))
      (node (ref "X33") (pin "2") (pinfunction "2_2") (pintype "passive"))
    )
    (net (code "62") (name "Net-(R61-Pad2)") (class "Default")
      (node (ref "R61") (pin "2") (pinfunction "2_2") (pintype "passive"))
      (node (ref "VD2") (pin "3") (pintype "passive"))
    )
    (net (code "63") (name "Net-(R68-Pad1)") (class "Default")
      (node (ref "R68") (pin "1") (pinfunction "1_1") (pintype "passive"))
      (node (ref "X34") (pin "2") (pinfunction "2_2") (pintype "passive"))
    )
    (net (code "64") (name "Net-(R69-Pad2)") (class "Default")
      (node (ref "R69") (pin "2") (pinfunction "2_2") (pintype "passive"))
      (node (ref "X35") (pin "1") (pinfunction "1_1") (pintype "passive"))
    )
    (net (code "65") (name "Net-(X36-Pad2)") (class "Default")
      (node (ref "X36") (pin "2") (pinfunction "2_2") (pintype "passive"))
      (node (ref "XP11") (pin "8") (pinfunction "8_8") (pintype "passive"))
    )
    (net (code "66") (name "Net-(X37-Pad2)") (class "Default")
      (node (ref "X37") (pin "2") (pinfunction "2_2") (pintype "passive"))
      (node (ref "XP12") (pin "8") (pinfunction "8_8") (pintype "passive"))
    )
    (net (code "67") (name "VIS1") (class "Default")
      (node (ref "C53") (pin "1") (pinfunction "1_1") (pintype "passive"))
      (node (ref "C54") (pin "2") (pinfunction "2_2") (pintype "passive"))
      (node (ref "C55") (pin "1") (pinfunction "1_1") (pintype "passive"))
      (node (ref "C56") (pin "1") (pinfunction "+_1") (pintype "passive"))
      (node (ref "DD9") (pin "10") (pinfunction "VISOout_10") (pintype "power_in"))
      (node (ref "DD9") (pin "15") (pinfunction "VISOin_15") (pintype "power_in"))
      (node (ref "R52") (pin "2") (pinfunction "2_2") (pintype "passive"))
    )
    (net (code "68") (name "VIS2") (class "Default")
      (node (ref "C77") (pin "1") (pinfunction "1_1") (pintype "passive"))
      (node (ref "C78") (pin "2") (pinfunction "2_2") (pintype "passive"))
      (node (ref "C79") (pin "1") (pinfunction "1_1") (pintype "passive"))
      (node (ref "C80") (pin "1") (pinfunction "+_1") (pintype "passive"))
      (node (ref "DD11") (pin "10") (pinfunction "VISOout_10") (pintype "power_in"))
      (node (ref "DD11") (pin "15") (pinfunction "VISOin_15") (pintype "power_in"))
      (node (ref "R70") (pin "2") (pinfunction "2_2") (pintype "passive"))
    )
    (net (code "69") (name "unconnected-(DD10-NC-Pad27)") (class "Default")
      (node (ref "DD10") (pin "27") (pinfunction "NC_27") (pintype "passive"))
    )
    (net (code "70") (name "unconnected-(XS6-Pad4)") (class "Default")
      (node (ref "XS6") (pin "4") (pinfunction "4_4") (pintype "passive"))
    )
    (net (code "71") (name "unconnected-(XS6-Pad5)") (class "Default")
      (node (ref "XS6") (pin "5") (pinfunction "5_5") (pintype "passive"))
    )
  )
)
